# STM32F405.net
KiCad netlist of a schematic drawn in Altium Designer
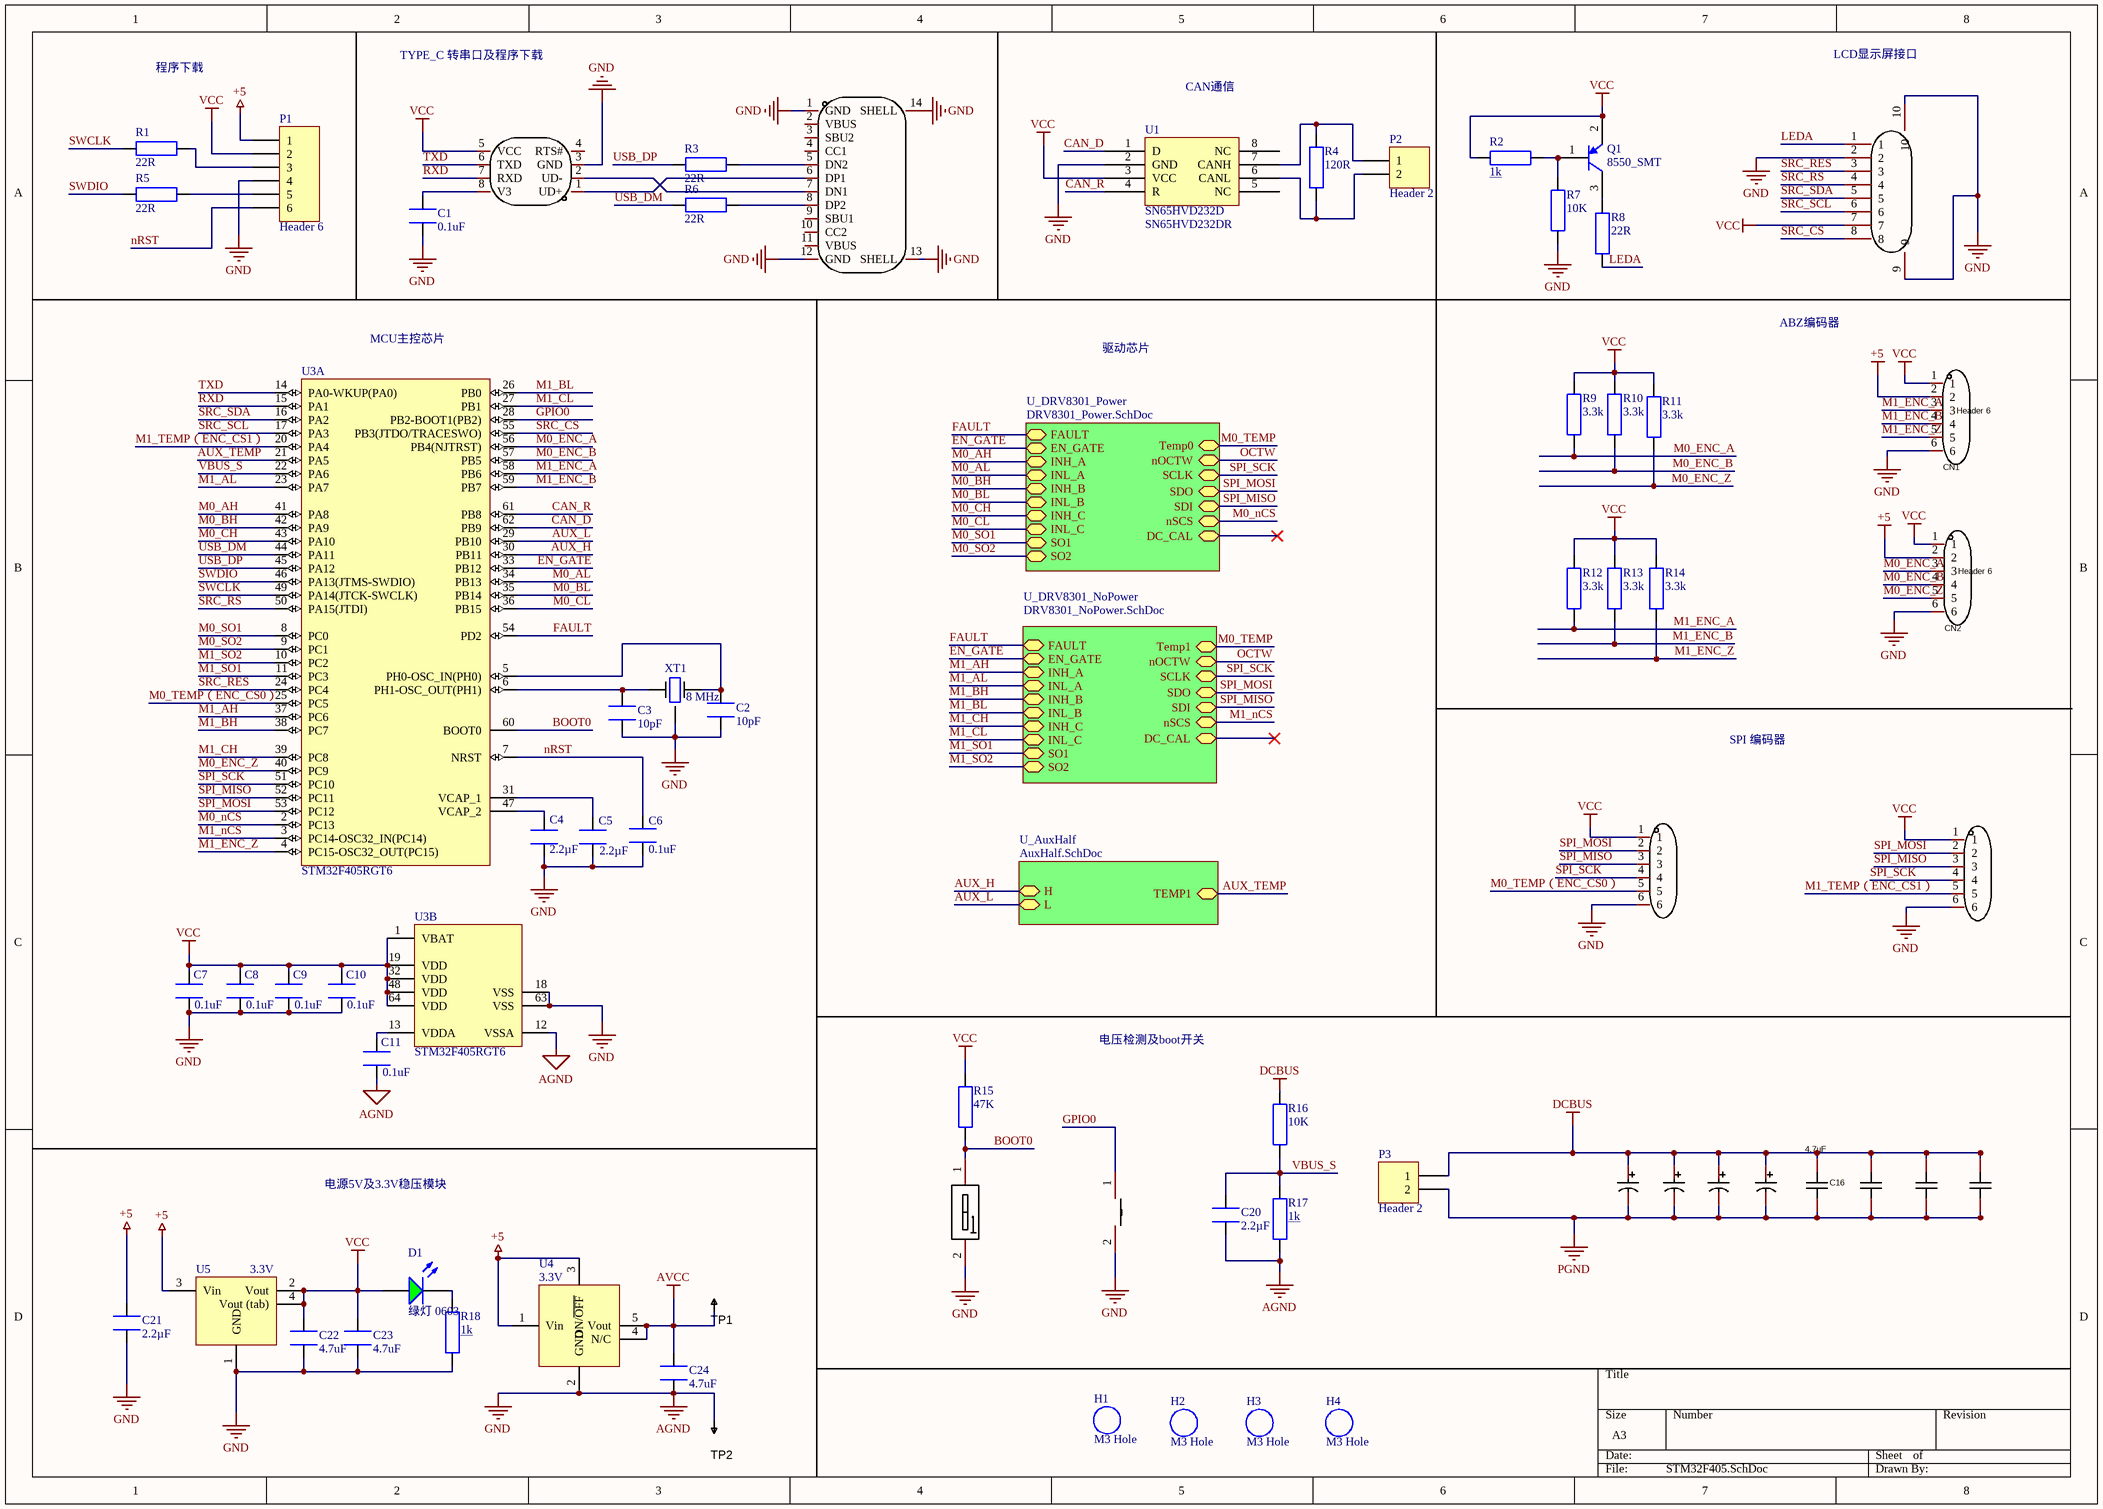
[diagram p0: STM32F405.SchDoc]

(export (version "E")
  (design (tool "Eeschema 10.0.6"))
  (components
    (comp (ref "C1")
      (value "0.1uF")
      (footprint "CAPC1608X09L")
      (description "CAP CER 0.1UF 50V X7R 0603")
      (fields
        (field (name "MANUFACTURER") "Murata Electronics North America")
        (field (name "MANUFACTURER PART NUMBER") "GRM188R71H104KA93D")
      )
      (libsource (lib "two_ax_PCB") (part "GRM188R71H104KA93D"))
    )
    (comp (ref "C2")
      (value "10pF")
      (footprint "CAPC1608X09L")
      (description "CAP CER 10PF 50V NP0 0603")
      (fields
        (field (name "MANUFACTURER") "Murata Electronics North America")
        (field (name "MANUFACTURER PART NUMBER") "GRM1885C1H100JA01D")
      )
      (libsource (lib "two_ax_PCB") (part "GRM1885C1H100JA01D"))
    )
    (comp (ref "C3")
      (value "10pF")
      (footprint "CAPC1608X09L")
      (description "CAP CER 10PF 50V NP0 0603")
      (fields
        (field (name "MANUFACTURER") "Murata Electronics North America")
        (field (name "MANUFACTURER PART NUMBER") "GRM1885C1H100JA01D")
      )
      (libsource (lib "two_ax_PCB") (part "GRM1885C1H100JA01D"))
    )
    (comp (ref "C4")
      (value "2.2µF")
      (footprint "CAPC1608X09L")
      (description "CAP CER 2.2UF 16V X5R 0603")
      (fields
        (field (name "MANUFACTURER") "Murata Electronics North America")
        (field (name "MANUFACTURER PART NUMBER") "GRM188R61C225KE15D")
      )
      (libsource (lib "two_ax_PCB") (part "GRM188R61C225KE15D"))
    )
    (comp (ref "C5")
      (value "2.2µF")
      (footprint "CAPC1608X09L")
      (description "CAP CER 2.2UF 16V X5R 0603")
      (fields
        (field (name "MANUFACTURER") "Murata Electronics North America")
        (field (name "MANUFACTURER PART NUMBER") "GRM188R61C225KE15D")
      )
      (libsource (lib "two_ax_PCB") (part "GRM188R61C225KE15D"))
    )
    (comp (ref "C6")
      (value "0.1uF")
      (footprint "CAPC1608X09L")
      (description "CAP CER 0.1UF 50V X7R 0603")
      (fields
        (field (name "MANUFACTURER") "Murata Electronics North America")
        (field (name "MANUFACTURER PART NUMBER") "GRM188R71H104KA93D")
      )
      (libsource (lib "two_ax_PCB") (part "GRM188R71H104KA93D"))
    )
    (comp (ref "C7")
      (value "0.1uF")
      (footprint "CAPC1608X09L")
      (description "CAP CER 0.1UF 50V X7R 0603")
      (fields
        (field (name "MANUFACTURER") "Murata Electronics North America")
        (field (name "MANUFACTURER PART NUMBER") "GRM188R71H104KA93D")
      )
      (libsource (lib "two_ax_PCB") (part "GRM188R71H104KA93D"))
    )
    (comp (ref "C8")
      (value "0.1uF")
      (footprint "CAPC1608X09L")
      (description "CAP CER 0.1UF 50V X7R 0603")
      (fields
        (field (name "MANUFACTURER") "Murata Electronics North America")
        (field (name "MANUFACTURER PART NUMBER") "GRM188R71H104KA93D")
      )
      (libsource (lib "two_ax_PCB") (part "GRM188R71H104KA93D"))
    )
    (comp (ref "C9")
      (value "0.1uF")
      (footprint "CAPC1608X09L")
      (description "CAP CER 0.1UF 50V X7R 0603")
      (fields
        (field (name "MANUFACTURER") "Murata Electronics North America")
        (field (name "MANUFACTURER PART NUMBER") "GRM188R71H104KA93D")
      )
      (libsource (lib "two_ax_PCB") (part "GRM188R71H104KA93D"))
    )
    (comp (ref "C10")
      (value "0.1uF")
      (footprint "CAPC1608X09L")
      (description "CAP CER 0.1UF 50V X7R 0603")
      (fields
        (field (name "MANUFACTURER") "Murata Electronics North America")
        (field (name "MANUFACTURER PART NUMBER") "GRM188R71H104KA93D")
      )
      (libsource (lib "two_ax_PCB") (part "GRM188R71H104KA93D"))
    )
    (comp (ref "C11")
      (value "0.1uF")
      (footprint "CAPC1608X09L")
      (description "CAP CER 0.1UF 50V X7R 0603")
      (fields
        (field (name "MANUFACTURER") "Murata Electronics North America")
        (field (name "MANUFACTURER PART NUMBER") "GRM188R71H104KA93D")
      )
      (libsource (lib "two_ax_PCB") (part "GRM188R71H104KA93D"))
    )
    (comp (ref "C12")
      (value "220uF")
      (footprint "CAP-SMD_BD12.5-L13.0-W13.0-FD")
      (description "63v 220uF 贴片电容")
      (fields (field (name "MANUFACTURER") "lelon(立隆)") (field (name "MANUFACTURER PART") "VZH221M1JTR-1313"))
      (libsource (lib "CustomComponents") (part "VZH221M1JTR-1313"))
    )
    (comp (ref "C13")
      (value "220uF")
      (footprint "CAP-SMD_BD12.5-L13.0-W13.0-FD")
      (description "63v 220uF 贴片电容")
      (fields (field (name "MANUFACTURER") "lelon(立隆)") (field (name "MANUFACTURER PART") "VZH221M1JTR-1313"))
      (libsource (lib "CustomComponents") (part "VZH221M1JTR-1313"))
    )
    (comp (ref "C14")
      (value "220uF")
      (footprint "CAP-SMD_BD12.5-L13.0-W13.0-FD")
      (description "63v 220uF 贴片电容")
      (fields (field (name "MANUFACTURER") "lelon(立隆)") (field (name "MANUFACTURER PART") "VZH221M1JTR-1313"))
      (libsource (lib "CustomComponents") (part "VZH221M1JTR-1313"))
    )
    (comp (ref "C15")
      (value "220uF")
      (footprint "CAP-SMD_BD12.5-L13.0-W13.0-FD")
      (description "63v 220uF 贴片电容")
      (fields (field (name "MANUFACTURER") "lelon(立隆)") (field (name "MANUFACTURER PART") "VZH221M1JTR-1313"))
      (libsource (lib "CustomComponents") (part "VZH221M1JTR-1313"))
    )
    (comp (ref "C16")
      (value "4.7uF")
      (footprint "C1210")
      (description "4.7uF 63V 1210封装")
      (fields
        (field (name "MANUFACTURER") "SANYEAR(叁叶源)")
        (field (name "MANUFACTURER PART") "C1210X7R475K630NT")
      )
      (libsource (lib "CustomComponents") (part "C1210X7R475K630NT"))
    )
    (comp (ref "C17")
      (value "4.7uF")
      (footprint "C1210")
      (description "4.7uF 63V 1210封装")
      (fields
        (field (name "MANUFACTURER") "SANYEAR(叁叶源)")
        (field (name "MANUFACTURER PART") "C1210X7R475K630NT")
      )
      (libsource (lib "CustomComponents") (part "C1210X7R475K630NT"))
    )
    (comp (ref "C18")
      (value "4.7uF")
      (footprint "C1210")
      (description "4.7uF 63V 1210封装")
      (fields
        (field (name "MANUFACTURER") "SANYEAR(叁叶源)")
        (field (name "MANUFACTURER PART") "C1210X7R475K630NT")
      )
      (libsource (lib "CustomComponents") (part "C1210X7R475K630NT"))
    )
    (comp (ref "C19")
      (value "4.7uF")
      (footprint "C1210")
      (description "4.7uF 63V 1210封装")
      (fields
        (field (name "MANUFACTURER") "SANYEAR(叁叶源)")
        (field (name "MANUFACTURER PART") "C1210X7R475K630NT")
      )
      (libsource (lib "CustomComponents") (part "C1210X7R475K630NT"))
    )
    (comp (ref "C20")
      (value "2.2µF")
      (footprint "CAPC1608X09L")
      (description "CAP CER 2.2UF 16V X5R 0603")
      (fields
        (field (name "MANUFACTURER") "Murata Electronics North America")
        (field (name "MANUFACTURER PART NUMBER") "GRM188R61C225KE15D")
      )
      (libsource (lib "CustomComponents") (part "GRM188R61C225KE15D"))
    )
    (comp (ref "C21")
      (value "2.2µF")
      (footprint "CAPC1608X09L")
      (description "CAP CER 2.2UF 16V X5R 0603")
      (fields
        (field (name "MANUFACTURER") "Murata Electronics North America")
        (field (name "MANUFACTURER PART NUMBER") "GRM188R61C225KE15D")
      )
      (libsource (lib "CustomComponents") (part "GRM188R61C225KE15D"))
    )
    (comp (ref "C22")
      (value "4.7uF")
      (footprint "CAPC2012X09N")
      (description "CAP CER 4.7UF 50V X5R 0805")
      (fields
        (field (name "MANUFACTURER") "Murata Electronics North America")
        (field (name "TOLERANCE") "±10%")
      )
      (libsource (lib "CustomComponents") (part "GRM21BR61H475KE51L"))
    )
    (comp (ref "C23")
      (value "4.7uF")
      (footprint "CAPC2012X09N")
      (description "CAP CER 4.7UF 50V X5R 0805")
      (fields
        (field (name "MANUFACTURER") "Murata Electronics North America")
        (field (name "TOLERANCE") "±10%")
      )
      (libsource (lib "CustomComponents") (part "GRM21BR61H475KE51L"))
    )
    (comp (ref "C24")
      (value "4.7uF")
      (footprint "CAPC2012X09N")
      (description "CAP CER 4.7UF 50V X5R 0805")
      (fields
        (field (name "MANUFACTURER") "Murata Electronics North America")
        (field (name "TOLERANCE") "±10%")
      )
      (libsource (lib "CustomComponents") (part "GRM21BR61H475KE51L"))
    )
    (comp (ref "CN1")
      (value "Header 6")
      (footprint "XH254-6")
      (description "6p 90度弯插")
      (fields
        (field (name "MANUFACTURER") "XKB Connection(中国星坤)")
        (field (name "MANUFACTURER PART") "X8821WR-06S-N0SN")
      )
      (libsource (lib "CustomComponents") (part "X8821WR-06S-N0SN"))
    )
    (comp (ref "CN2")
      (value "Header 6")
      (footprint "XH254-6")
      (description "6p 90度弯插")
      (fields
        (field (name "MANUFACTURER") "XKB Connection(中国星坤)")
        (field (name "MANUFACTURER PART") "X8821WR-06S-N0SN")
      )
      (libsource (lib "CustomComponents") (part "X8821WR-06S-N0SN"))
    )
    (comp (ref "CN3")
      (value "X8821WR-06S-N0SN")
      (footprint "CONN-TH_6P-P2.50_X8821WR-06S-N2SN")
      (description "6p 90度弯插")
      (fields (field (name "MANUFACTURER") "XKB Connection(中国星坤)"))
      (libsource (lib "CustomComponents") (part "X8821WR-06S-N0SN"))
    )
    (comp (ref "CN4")
      (value "X8821WR-06S-N0SN")
      (footprint "CONN-TH_6P-P2.50_X8821WR-06S-N2SN")
      (description "6p 90度弯插")
      (fields (field (name "MANUFACTURER") "XKB Connection(中国星坤)"))
      (libsource (lib "CustomComponents") (part "X8821WR-06S-N0SN"))
    )
    (comp (ref "D1")
      (value "绿灯 0603")
      (footprint "0603_LED_S1")
      (description "发光二极管")
      (libsource (lib "02-Miscellaneous_Devices_ZSF_Library") (part "0603 绿灯"))
    )
    (comp (ref "FPC1")
      (value "AFC01-S08FCA-00")
      (footprint "FPC-SMD_P0.50-8P_FGS-XJ-H2.0")
      (description "显示屏 8P FPC接口")
      (fields (field (name "MANUFACTURER") "JS(钜硕电子)"))
      (libsource (lib "CustomComponents") (part "AFC01-S08FCA-00"))
    )
    (comp (ref "H1")
      (value "M3 Hole")
      (footprint "M3 Hole")
      (description "M3 Hole with no copper")
      (libsource (lib "two_ax_PCB") (part "M3 Hole"))
    )
    (comp (ref "H2")
      (value "M3 Hole")
      (footprint "M3 Hole")
      (description "M3 Hole with no copper")
      (libsource (lib "two_ax_PCB") (part "M3 Hole"))
    )
    (comp (ref "H3")
      (value "M3 Hole")
      (footprint "M3 Hole")
      (description "M3 Hole with no copper")
      (libsource (lib "two_ax_PCB") (part "M3 Hole"))
    )
    (comp (ref "H4")
      (value "M3 Hole")
      (footprint "M3 Hole")
      (description "M3 Hole with no copper")
      (libsource (lib "two_ax_PCB") (part "M3 Hole"))
    )
    (comp (ref "P1")
      (value "Header 6")
      (footprint "SIP-6")
      (description "Header, 6-Pin")
      (fields (field (name "PUBLISHER") "Altium Limited"))
      (libsource (lib "01-Connect_IntegratedLibrary") (part "Header 6"))
    )
    (comp (ref "P2")
      (value "Header 2")
      (footprint "XH254-2")
      (description "Header, 2-Pin")
      (fields (field (name "PUBLISHER") "Altium Limited"))
      (libsource (lib "") (part "Header 2_1"))
    )
    (comp (ref "P3")
      (value "Header 2")
      (footprint "CONN-TH_XT30U-M")
      (description "Header, 2-Pin")
      (fields (field (name "PUBLISHER") "Altium Limited"))
      (libsource (lib "01-Connect_IntegratedLibrary") (part "Header 2"))
    )
    (comp (ref "Q1")
      (value "8550_SMT")
      (footprint "SOT-23(SOT-23-3)")
      (description "PNP型小功率三极管")
      (libsource (lib "02-Miscellaneous_Devices_ZSF_Library") (part "8550_SOT-23"))
    )
    (comp (ref "R1")
      (value "22R")
      (footprint "RESC1608X55N")
      (description "RES SMD 22 OHM 1% 1/10W 0603")
      (fields
        (field (name "MANUFACTURER") "Yageo")
        (field (name "MANUFACTURER PART NUMBER") "RC0603FR-0722RL")
      )
      (libsource (lib "CustomComponents") (part "RC0603FR-0722RL"))
    )
    (comp (ref "R2")
      (value "1k")
      (footprint "RESC1608X55N")
      (description "RES SMD 1K OHM 1% 1/10W 0603")
      (fields (field (name "MANUFACTURER") "Yageo") (field (name "TOLERANCE") "±1%"))
      (libsource (lib "CustomComponents") (part "RC0603FR-071KL"))
    )
    (comp (ref "R3")
      (value "22R")
      (footprint "RESC1608X55N")
      (description "RES SMD 22 OHM 1% 1/10W 0603")
      (fields
        (field (name "MANUFACTURER") "Yageo")
        (field (name "MANUFACTURER PART NUMBER") "RC0603FR-0722RL")
      )
      (libsource (lib "CustomComponents") (part "RC0603FR-0722RL"))
    )
    (comp (ref "R4")
      (value "120R")
      (footprint "RESC1608X55N")
      (description "RES SMD 120 OHM 1% 1/10W 0603")
      (fields
        (field (name "MANUFACTURER") "Yageo")
        (field (name "MANUFACTURER PART NUMBER") "RC0603FR-07120RL")
      )
      (libsource (lib "CustomComponents") (part "RC0603FR-07120RL"))
    )
    (comp (ref "R5")
      (value "22R")
      (footprint "RESC1608X55N")
      (description "RES SMD 22 OHM 1% 1/10W 0603")
      (fields
        (field (name "MANUFACTURER") "Yageo")
        (field (name "MANUFACTURER PART NUMBER") "RC0603FR-0722RL")
      )
      (libsource (lib "CustomComponents") (part "RC0603FR-0722RL"))
    )
    (comp (ref "R6")
      (value "22R")
      (footprint "RESC1608X55N")
      (description "RES SMD 22 OHM 1% 1/10W 0603")
      (fields
        (field (name "MANUFACTURER") "Yageo")
        (field (name "MANUFACTURER PART NUMBER") "RC0603FR-0722RL")
      )
      (libsource (lib "CustomComponents") (part "RC0603FR-0722RL"))
    )
    (comp (ref "R7")
      (value "10K")
      (footprint "RESC1608X55N")
      (description "RES SMD 10K OHM 1% 1/10W 0603")
      (fields
        (field (name "MANUFACTURER") "Yageo")
        (field (name "MANUFACTURER PART NUMBER") "RC0603FR-0710KL")
      )
      (libsource (lib "CustomComponents") (part "RC0603FR-0710KL"))
    )
    (comp (ref "R8")
      (value "22R")
      (footprint "RESC1608X55N")
      (description "RES SMD 22 OHM 1% 1/10W 0603")
      (fields
        (field (name "MANUFACTURER") "Yageo")
        (field (name "MANUFACTURER PART NUMBER") "RC0603FR-0722RL")
      )
      (libsource (lib "CustomComponents") (part "RC0603FR-0722RL"))
    )
    (comp (ref "R9")
      (value "3.3k")
      (footprint "RESC1608X55N")
      (description "RES SMD 3.3K OHM 1% 1/10W 0603")
      (fields
        (field (name "MANUFACTURER") "Yageo")
        (field (name "MANUFACTURER PART NUMBER") "RC0603FR-073K3L")
      )
      (libsource (lib "CustomComponents") (part "RC0603FR-073K3L"))
    )
    (comp (ref "R10")
      (value "3.3k")
      (footprint "RESC1608X55N")
      (description "RES SMD 3.3K OHM 1% 1/10W 0603")
      (fields
        (field (name "MANUFACTURER") "Yageo")
        (field (name "MANUFACTURER PART NUMBER") "RC0603FR-073K3L")
      )
      (libsource (lib "CustomComponents") (part "RC0603FR-073K3L"))
    )
    (comp (ref "R11")
      (value "3.3k")
      (footprint "RESC1608X55N")
      (description "RES SMD 3.3K OHM 1% 1/10W 0603")
      (fields
        (field (name "MANUFACTURER") "Yageo")
        (field (name "MANUFACTURER PART NUMBER") "RC0603FR-073K3L")
      )
      (libsource (lib "CustomComponents") (part "RC0603FR-073K3L"))
    )
    (comp (ref "R12")
      (value "3.3k")
      (footprint "RESC1608X55N")
      (description "RES SMD 3.3K OHM 1% 1/10W 0603")
      (fields
        (field (name "MANUFACTURER") "Yageo")
        (field (name "MANUFACTURER PART NUMBER") "RC0603FR-073K3L")
      )
      (libsource (lib "CustomComponents") (part "RC0603FR-073K3L"))
    )
    (comp (ref "R13")
      (value "3.3k")
      (footprint "RESC1608X55N")
      (description "RES SMD 3.3K OHM 1% 1/10W 0603")
      (fields
        (field (name "MANUFACTURER") "Yageo")
        (field (name "MANUFACTURER PART NUMBER") "RC0603FR-073K3L")
      )
      (libsource (lib "CustomComponents") (part "RC0603FR-073K3L"))
    )
    (comp (ref "R14")
      (value "3.3k")
      (footprint "RESC1608X55N")
      (description "RES SMD 3.3K OHM 1% 1/10W 0603")
      (fields
        (field (name "MANUFACTURER") "Yageo")
        (field (name "MANUFACTURER PART NUMBER") "RC0603FR-073K3L")
      )
      (libsource (lib "CustomComponents") (part "RC0603FR-073K3L"))
    )
    (comp (ref "R15")
      (value "47K")
      (footprint "RESC1608X55N")
      (description "RES SMD 47K OHM 1% 1/10W 0603")
      (fields
        (field (name "MANUFACTURER") "Yageo")
        (field (name "MANUFACTURER PART NUMBER") "RC0603FR-0747KL")
      )
      (libsource (lib "two_ax_PCB") (part "RC0603FR-0747KL"))
    )
    (comp (ref "R16")
      (value "10K")
      (footprint "RESC1608X55N")
      (description "RES SMD 10K OHM 1% 1/10W 0603")
      (fields
        (field (name "MANUFACTURER") "Yageo")
        (field (name "MANUFACTURER PART NUMBER") "RC0603FR-0710KL")
      )
      (libsource (lib "CustomComponents") (part "RC0603FR-0710KL"))
    )
    (comp (ref "R17")
      (value "1k")
      (footprint "RESC1608X55N")
      (description "RES SMD 1K OHM 1% 1/10W 0603")
      (fields (field (name "MANUFACTURER") "Yageo") (field (name "TOLERANCE") "±1%"))
      (libsource (lib "CustomComponents") (part "RC0603FR-071KL"))
    )
    (comp (ref "R18")
      (value "1k")
      (footprint "RESC1608X55N")
      (description "RES SMD 1K OHM 1% 1/10W 0603")
      (fields (field (name "MANUFACTURER") "Yageo") (field (name "TOLERANCE") "±1%"))
      (libsource (lib "CustomComponents") (part "RC0603FR-071KL"))
    )
    (comp (ref "SW1")
      (value "DSWB01LHGET")
      (footprint "SW-TH_DSWB01LHGET")
      (description "单刀拨码开关")
      (fields (field (name "MANUFACTURER") "YE"))
      (libsource (lib "CustomComponents") (part "DSWB01LHGET"))
    )
    (comp (ref "SW2")
      (value "TS-1101-C-W")
      (footprint "SW-SMD_L6.0-W3.3-LS8.0")
      (description "轻触开关")
      (fields (field (name "MANUFACTURER") "XKB Connectivity(中国星坤)"))
      (libsource (lib "CustomComponents") (part "TS-1101-C-W"))
    )
    (comp (ref "TP1")
      (value "TESTPOINT")
      (footprint "TP-R30")
      (description "SMD test pin")
      (libsource (lib "two_ax_PCB") (part "TESTPOINT"))
    )
    (comp (ref "TP2")
      (value "TESTPOINT")
      (footprint "TP-R30")
      (description "SMD test pin")
      (libsource (lib "two_ax_PCB") (part "TESTPOINT"))
    )
    (comp (ref "U1")
      (value "SN65HVD232D")
      (footprint "SOIC127P600X175-8N")
      (fields
        (field (name "MANUFACTURER") "Texas Instruments")
        (field (name "MANUFACTURER PART NUMBER") "SN65HVD232DR")
      )
      (libsource (lib "CustomComponents") (part "SN65HVD232D"))
    )
    (comp (ref "U2")
      (value "CH340N")
      (footprint "ch340N  SOP-8_L4.9-W3.9-P1.27-LS6.0-BL")
      (fields (field (name "MANUFACTURER") "WCH(南京沁恒)"))
      (libsource (lib "CustomComponents") (part "CH340N"))
    )
    (comp (ref "U3")
      (value "STM32F405RGT6")
      (footprint "STM-LQFP64_N")
      (fields (field (name "MANUFACTURER") "STMicroelectronics"))
      (libsource (lib "STMicroelectronics STM32 F4") (part "STM32F405RGT6"))
    )
    (comp (ref "U4")
      (value "3.3V")
      (footprint "SOT23-5")
      (description "IC REG LDO 3.3V 0.25A SOT23-5")
      (fields (field (name "MANUFACTURER") "Texas Instruments"))
      (libsource (lib "CustomComponents") (part "LP5907MFX-3.3/NOPB"))
    )
    (comp (ref "U5")
      (value "3.3V")
      (footprint "SOT223")
      (description "IC REG LDO 3.3V 1A SOT223")
      (fields (field (name "MANUFACTURER") "Diodes Incorporated"))
      (libsource (lib "CustomComponents") (part "AZ1117EH-3.3TRG1"))
    )
    (comp (ref "USB1")
      (value "TYPE-C 16PIN 2MD(073)")
      (footprint "USB-C-SMD_TYPE-C-16PIN-2MD-073")
      (fields (field (name "MANUFACTURER") "SHOU HAN(首韩)"))
      (libsource (lib "CustomComponents") (part "TYPE-C 16PIN 2MD(073)"))
    )
    (comp (ref "XT1")
      (value "8 MHz")
      (footprint "DFN220P320X110-4N")
      (description "Crystal 8MHz ±10ppm 10pF 200 Ohm -10°C ~ 60°C Surface Mount 4-SMD, No Lead (DFN, LCC)")
      (fields
        (field (name "MANUFACTURER") "Abracon LLC")
        (field (name "MANUFACTURER PART NUMBER") "ABM3B-8.000MHZ-10-1-U-T")
      )
      (libsource (lib "two_ax_PCB") (part "ABM3B-8.000MHZ-10-1-U-T"))
    )
  )
  (nets
    (net (code "1") (name "+5") (class "Default")
      (node (ref "C21") (pin "2") (pinfunction "2_2") (pintype "passive"))
      (node (ref "CN1") (pin "2") (pinfunction "2_2") (pintype "passive"))
      (node (ref "CN2") (pin "2") (pinfunction "2_2") (pintype "passive"))
      (node (ref "P1") (pin "1") (pinfunction "1_1") (pintype "passive"))
      (node (ref "U4") (pin "1") (pinfunction "Vin_1") (pintype "passive"))
      (node (ref "U4") (pin "3") (pinfunction "ON/~{OFF}_3") (pintype "passive"))
      (node (ref "U5") (pin "3") (pinfunction "Vin_3") (pintype "passive"))
    )
    (net (code "2") (name "/AUX_H") (class "Default")
      (node (ref "U3") (pin "30") (pinfunction "PB11_30") (pintype "bidirectional"))
    )
    (net (code "3") (name "/AUX_L") (class "Default")
      (node (ref "U3") (pin "29") (pinfunction "PB10_29") (pintype "bidirectional"))
    )
    (net (code "4") (name "/AUX_TEMP") (class "Default")
      (node (ref "U3") (pin "21") (pinfunction "PA5_21") (pintype "bidirectional"))
    )
    (net (code "5") (name "/BOOT0") (class "Default")
      (node (ref "R15") (pin "1") (pinfunction "0_1") (pintype "passive"))
      (node (ref "SW1") (pin "1") (pinfunction "A1_1") (pintype "passive"))
      (node (ref "U3") (pin "60") (pinfunction "BOOT0_60") (pintype "passive"))
    )
    (net (code "6") (name "/CAN_D") (class "Default")
      (node (ref "U1") (pin "1") (pinfunction "D_1") (pintype "passive"))
      (node (ref "U3") (pin "62") (pinfunction "PB9_62") (pintype "bidirectional"))
    )
    (net (code "7") (name "/CAN_R") (class "Default")
      (node (ref "U1") (pin "4") (pinfunction "R_4") (pintype "passive"))
      (node (ref "U3") (pin "61") (pinfunction "PB8_61") (pintype "bidirectional"))
    )
    (net (code "10") (name "/EN_GATE") (class "Default")
      (node (ref "U3") (pin "33") (pinfunction "PB12_33") (pintype "bidirectional"))
    )
    (net (code "11") (name "/FAULT") (class "Default")
      (node (ref "U3") (pin "54") (pinfunction "PD2_54") (pintype "bidirectional"))
    )
    (net (code "12") (name "/GPIO0") (class "Default")
      (node (ref "SW2") (pin "1") (pinfunction "1_1") (pintype "passive"))
      (node (ref "U3") (pin "28") (pinfunction "PB2-BOOT1(PB2)_28") (pintype "bidirectional"))
    )
    (net (code "13") (name "/LEDA") (class "Default")
      (node (ref "FPC1") (pin "1") (pinfunction "1_1") (pintype "passive"))
      (node (ref "R8") (pin "1") (pinfunction "0_1") (pintype "passive"))
    )
    (net (code "14") (name "/M0_AH") (class "Default")
      (node (ref "U3") (pin "41") (pinfunction "PA8_41") (pintype "bidirectional"))
    )
    (net (code "15") (name "/M0_AL") (class "Default")
      (node (ref "U3") (pin "34") (pinfunction "PB13_34") (pintype "bidirectional"))
    )
    (net (code "16") (name "/M0_BH") (class "Default")
      (node (ref "U3") (pin "42") (pinfunction "PA9_42") (pintype "bidirectional"))
    )
    (net (code "17") (name "/M0_BL") (class "Default")
      (node (ref "U3") (pin "35") (pinfunction "PB14_35") (pintype "bidirectional"))
    )
    (net (code "18") (name "/M0_CH") (class "Default")
      (node (ref "U3") (pin "43") (pinfunction "PA10_43") (pintype "bidirectional"))
    )
    (net (code "19") (name "/M0_CL") (class "Default")
      (node (ref "U3") (pin "36") (pinfunction "PB15_36") (pintype "bidirectional"))
    )
    (net (code "20") (name "/M0_ENC_A") (class "Default")
      (node (ref "CN2") (pin "3") (pinfunction "3_3") (pintype "passive"))
      (node (ref "R9") (pin "1") (pinfunction "0_1") (pintype "passive"))
      (node (ref "U3") (pin "56") (pinfunction "PB4(NJTRST)_56") (pintype "bidirectional"))
    )
    (net (code "21") (name "/M0_ENC_B") (class "Default")
      (node (ref "CN2") (pin "4") (pinfunction "4_4") (pintype "passive"))
      (node (ref "R10") (pin "1") (pinfunction "0_1") (pintype "passive"))
      (node (ref "U3") (pin "57") (pinfunction "PB5_57") (pintype "bidirectional"))
    )
    (net (code "22") (name "/M0_ENC_Z") (class "Default")
      (node (ref "CN2") (pin "5") (pinfunction "5_5") (pintype "passive"))
      (node (ref "R11") (pin "1") (pinfunction "0_1") (pintype "passive"))
      (node (ref "U3") (pin "40") (pinfunction "PC9_40") (pintype "bidirectional"))
    )
    (net (code "23") (name "/M0_SO1") (class "Default")
      (node (ref "U3") (pin "8") (pinfunction "PC0_8") (pintype "bidirectional"))
    )
    (net (code "24") (name "/M0_SO2") (class "Default")
      (node (ref "U3") (pin "9") (pinfunction "PC1_9") (pintype "bidirectional"))
    )
    (net (code "26") (name "/M0_TEMP（ENC_CS0）") (class "Default")
      (node (ref "CN3") (pin "5") (pinfunction "5_5") (pintype "passive"))
      (node (ref "U3") (pin "25") (pinfunction "PC5_25") (pintype "bidirectional"))
    )
    (net (code "27") (name "/M0_nCS") (class "Default")
      (node (ref "U3") (pin "2") (pinfunction "PC13_2") (pintype "bidirectional"))
    )
    (net (code "28") (name "/M1_AH") (class "Default")
      (node (ref "U3") (pin "37") (pinfunction "PC6_37") (pintype "bidirectional"))
    )
    (net (code "29") (name "/M1_AL") (class "Default")
      (node (ref "U3") (pin "23") (pinfunction "PA7_23") (pintype "bidirectional"))
    )
    (net (code "30") (name "/M1_BH") (class "Default")
      (node (ref "U3") (pin "38") (pinfunction "PC7_38") (pintype "bidirectional"))
    )
    (net (code "31") (name "/M1_BL") (class "Default")
      (node (ref "U3") (pin "26") (pinfunction "PB0_26") (pintype "bidirectional"))
    )
    (net (code "32") (name "/M1_CH") (class "Default")
      (node (ref "U3") (pin "39") (pinfunction "PC8_39") (pintype "bidirectional"))
    )
    (net (code "33") (name "/M1_CL") (class "Default")
      (node (ref "U3") (pin "27") (pinfunction "PB1_27") (pintype "bidirectional"))
    )
    (net (code "34") (name "/M1_ENC_A") (class "Default")
      (node (ref "CN1") (pin "3") (pinfunction "3_3") (pintype "passive"))
      (node (ref "R12") (pin "1") (pinfunction "0_1") (pintype "passive"))
      (node (ref "U3") (pin "58") (pinfunction "PB6_58") (pintype "bidirectional"))
    )
    (net (code "35") (name "/M1_ENC_B") (class "Default")
      (node (ref "CN1") (pin "4") (pinfunction "4_4") (pintype "passive"))
      (node (ref "R13") (pin "1") (pinfunction "0_1") (pintype "passive"))
      (node (ref "U3") (pin "59") (pinfunction "PB7_59") (pintype "bidirectional"))
    )
    (net (code "36") (name "/M1_ENC_Z") (class "Default")
      (node (ref "CN1") (pin "5") (pinfunction "5_5") (pintype "passive"))
      (node (ref "R14") (pin "1") (pinfunction "0_1") (pintype "passive"))
      (node (ref "U3") (pin "4") (pinfunction "PC15-OSC32_OUT(PC15)_4") (pintype "bidirectional"))
    )
    (net (code "37") (name "/M1_SO1") (class "Default")
      (node (ref "U3") (pin "11") (pinfunction "PC3_11") (pintype "bidirectional"))
    )
    (net (code "38") (name "/M1_SO2") (class "Default")
      (node (ref "U3") (pin "10") (pinfunction "PC2_10") (pintype "bidirectional"))
    )
    (net (code "39") (name "/M1_TEMP（ENC_CS1）") (class "Default")
      (node (ref "CN4") (pin "5") (pinfunction "5_5") (pintype "passive"))
      (node (ref "U3") (pin "20") (pinfunction "PA4_20") (pintype "bidirectional"))
    )
    (net (code "40") (name "/M1_nCS") (class "Default")
      (node (ref "U3") (pin "3") (pinfunction "PC14-OSC32_IN(PC14)_3") (pintype "bidirectional"))
    )
    (net (code "42") (name "/RXD") (class "Default")
      (node (ref "U2") (pin "7") (pinfunction "RXD_7") (pintype "passive"))
      (node (ref "U3") (pin "15") (pinfunction "PA1_15") (pintype "bidirectional"))
    )
    (net (code "43") (name "/SPI_MISO") (class "Default")
      (node (ref "CN3") (pin "3") (pinfunction "3_3") (pintype "passive"))
      (node (ref "CN4") (pin "3") (pinfunction "3_3") (pintype "passive"))
      (node (ref "U3") (pin "52") (pinfunction "PC11_52") (pintype "bidirectional"))
    )
    (net (code "44") (name "/SPI_MOSI") (class "Default")
      (node (ref "CN3") (pin "2") (pinfunction "2_2") (pintype "passive"))
      (node (ref "CN4") (pin "2") (pinfunction "2_2") (pintype "passive"))
      (node (ref "U3") (pin "53") (pinfunction "PC12_53") (pintype "bidirectional"))
    )
    (net (code "45") (name "/SPI_SCK") (class "Default")
      (node (ref "CN3") (pin "4") (pinfunction "4_4") (pintype "passive"))
      (node (ref "CN4") (pin "4") (pinfunction "4_4") (pintype "passive"))
      (node (ref "U3") (pin "51") (pinfunction "PC10_51") (pintype "bidirectional"))
    )
    (net (code "46") (name "/SRC_CS") (class "Default")
      (node (ref "FPC1") (pin "8") (pinfunction "8_8") (pintype "passive"))
      (node (ref "U3") (pin "55") (pinfunction "PB3(JTDO/TRACESWO)_55") (pintype "bidirectional"))
    )
    (net (code "47") (name "/SRC_RES") (class "Default")
      (node (ref "FPC1") (pin "3") (pinfunction "3_3") (pintype "passive"))
      (node (ref "U3") (pin "24") (pinfunction "PC4_24") (pintype "bidirectional"))
    )
    (net (code "48") (name "/SRC_RS") (class "Default")
      (node (ref "FPC1") (pin "4") (pinfunction "4_4") (pintype "passive"))
      (node (ref "U3") (pin "50") (pinfunction "PA15(JTDI)_50") (pintype "bidirectional"))
    )
    (net (code "49") (name "/SRC_SCL") (class "Default")
      (node (ref "FPC1") (pin "6") (pinfunction "6_6") (pintype "passive"))
      (node (ref "U3") (pin "17") (pinfunction "PA3_17") (pintype "bidirectional"))
    )
    (net (code "50") (name "/SRC_SDA") (class "Default")
      (node (ref "FPC1") (pin "5") (pinfunction "5_5") (pintype "passive"))
      (node (ref "U3") (pin "16") (pinfunction "PA2_16") (pintype "bidirectional"))
    )
    (net (code "51") (name "/SWCLK") (class "Default")
      (node (ref "R1") (pin "2") (pinfunction "0_2") (pintype "passive"))
      (node (ref "U3") (pin "49") (pinfunction "PA14(JTCK-SWCLK)_49") (pintype "bidirectional"))
    )
    (net (code "52") (name "/SWDIO") (class "Default")
      (node (ref "R5") (pin "2") (pinfunction "0_2") (pintype "passive"))
      (node (ref "U3") (pin "46") (pinfunction "PA13(JTMS-SWDIO)_46") (pintype "bidirectional"))
    )
    (net (code "53") (name "/TXD") (class "Default")
      (node (ref "U2") (pin "6") (pinfunction "TXD_6") (pintype "passive"))
      (node (ref "U3") (pin "14") (pinfunction "PA0-WKUP(PA0)_14") (pintype "bidirectional"))
    )
    (net (code "54") (name "/USB_DM") (class "Default")
      (node (ref "R6") (pin "2") (pinfunction "0_2") (pintype "passive"))
      (node (ref "U3") (pin "44") (pinfunction "PA11_44") (pintype "bidirectional"))
    )
    (net (code "55") (name "/USB_DP") (class "Default")
      (node (ref "R3") (pin "2") (pinfunction "0_2") (pintype "passive"))
      (node (ref "U3") (pin "45") (pinfunction "PA12_45") (pintype "bidirectional"))
    )
    (net (code "56") (name "/VBUS_S") (class "Default")
      (node (ref "C20") (pin "2") (pinfunction "2_2") (pintype "passive"))
      (node (ref "R16") (pin "1") (pinfunction "0_1") (pintype "passive"))
      (node (ref "R17") (pin "2") (pinfunction "0_2") (pintype "passive"))
      (node (ref "U3") (pin "22") (pinfunction "PA6_22") (pintype "bidirectional"))
    )
    (net (code "57") (name "/nRST") (class "Default")
      (node (ref "C6") (pin "2") (pinfunction "2_2") (pintype "passive"))
      (node (ref "P1") (pin "6") (pinfunction "6_6") (pintype "passive"))
      (node (ref "U3") (pin "7") (pinfunction "NRST_7") (pintype "bidirectional"))
    )
    (net (code "58") (name "AGND") (class "Default")
      (node (ref "C1") (pin "1") (pinfunction "1_1") (pintype "passive"))
      (node (ref "C10") (pin "1") (pinfunction "1_1") (pintype "passive"))
      (node (ref "C11") (pin "1") (pinfunction "1_1") (pintype "passive"))
      (node (ref "C2") (pin "2") (pinfunction "2_2") (pintype "passive"))
      (node (ref "C20") (pin "1") (pinfunction "1_1") (pintype "passive"))
      (node (ref "C21") (pin "1") (pinfunction "1_1") (pintype "passive"))
      (node (ref "C22") (pin "1") (pinfunction "1_1") (pintype "passive"))
      (node (ref "C23") (pin "1") (pinfunction "1_1") (pintype "passive"))
      (node (ref "C24") (pin "1") (pinfunction "1_1") (pintype "passive"))
      (node (ref "C3") (pin "2") (pinfunction "2_2") (pintype "passive"))
      (node (ref "C4") (pin "1") (pinfunction "1_1") (pintype "passive"))
      (node (ref "C5") (pin "1") (pinfunction "1_1") (pintype "passive"))
      (node (ref "C6") (pin "1") (pinfunction "1_1") (pintype "passive"))
      (node (ref "C7") (pin "1") (pinfunction "1_1") (pintype "passive"))
      (node (ref "C8") (pin "1") (pinfunction "1_1") (pintype "passive"))
      (node (ref "C9") (pin "1") (pinfunction "1_1") (pintype "passive"))
      (node (ref "CN1") (pin "6") (pinfunction "6_6") (pintype "passive"))
      (node (ref "CN2") (pin "6") (pinfunction "6_6") (pintype "passive"))
      (node (ref "CN3") (pin "6") (pinfunction "6_6") (pintype "passive"))
      (node (ref "CN4") (pin "6") (pinfunction "6_6") (pintype "passive"))
      (node (ref "FPC1") (pin "10") (pinfunction "10_10") (pintype "passive"))
      (node (ref "FPC1") (pin "2") (pinfunction "2_2") (pintype "passive"))
      (node (ref "FPC1") (pin "9") (pinfunction "9_9") (pintype "passive"))
      (node (ref "P1") (pin "4") (pinfunction "4_4") (pintype "passive"))
      (node (ref "R17") (pin "1") (pinfunction "0_1") (pintype "passive"))
      (node (ref "R18") (pin "1") (pinfunction "0_1") (pintype "passive"))
      (node (ref "R7") (pin "1") (pinfunction "0_1") (pintype "passive"))
      (node (ref "SW1") (pin "2") (pinfunction "2_2") (pintype "passive"))
      (node (ref "SW2") (pin "2") (pinfunction "2_2") (pintype "passive"))
      (node (ref "TP2") (pin "1") (pintype "passive"))
      (node (ref "U1") (pin "2") (pinfunction "GND_2") (pintype "passive"))
      (node (ref "U2") (pin "3") (pinfunction "GND_3") (pintype "passive"))
      (node (ref "U3") (pin "12") (pinfunction "VSSA_12") (pintype "power_in"))
      (node (ref "U3") (pin "18") (pinfunction "VSS_18") (pintype "power_in"))
      (node (ref "U3") (pin "63") (pinfunction "VSS_63") (pintype "power_in"))
      (node (ref "U4") (pin "2") (pinfunction "GND_2") (pintype "passive"))
      (node (ref "U5") (pin "1") (pinfunction "GND_1") (pintype "passive"))
      (node (ref "USB1") (pin "1") (pinfunction "GND_1") (pintype "passive"))
      (node (ref "USB1") (pin "12") (pinfunction "GND_12") (pintype "passive"))
      (node (ref "USB1") (pin "13") (pinfunction "SHELL_13") (pintype "passive"))
      (node (ref "USB1") (pin "14") (pinfunction "SHELL_14") (pintype "passive"))
      (node (ref "XT1") (pin "G") (pintype "passive"))
    )
    (net (code "59") (name "AVCC") (class "Default")
      (node (ref "C24") (pin "2") (pinfunction "2_2") (pintype "passive"))
      (node (ref "TP1") (pin "1") (pintype "passive"))
      (node (ref "U4") (pin "4") (pinfunction "N/C_4") (pintype "passive"))
      (node (ref "U4") (pin "5") (pinfunction "Vout_5") (pintype "passive"))
    )
    (net (code "60") (name "DCBUS") (class "Default")
      (node (ref "C12") (pin "1") (pinfunction "1_1") (pintype "passive"))
      (node (ref "C13") (pin "1") (pinfunction "1_1") (pintype "passive"))
      (node (ref "C14") (pin "1") (pinfunction "1_1") (pintype "passive"))
      (node (ref "C15") (pin "1") (pinfunction "1_1") (pintype "passive"))
      (node (ref "C16") (pin "1") (pinfunction "1_1") (pintype "passive"))
      (node (ref "C17") (pin "2") (pinfunction "2_2") (pintype "passive"))
      (node (ref "C18") (pin "2") (pinfunction "2_2") (pintype "passive"))
      (node (ref "C19") (pin "2") (pinfunction "2_2") (pintype "passive"))
      (node (ref "P3") (pin "1") (pinfunction "1_1") (pintype "passive"))
      (node (ref "R16") (pin "2") (pinfunction "0_2") (pintype "passive"))
    )
    (net (code "61") (name "Net-(D1-PadK)") (class "Default")
      (node (ref "D1") (pin "K") (pinfunction "K_K") (pintype "passive"))
      (node (ref "R18") (pin "2") (pinfunction "0_2") (pintype "passive"))
    )
    (net (code "62") (name "Net-(P1-Pad3)") (class "Default")
      (node (ref "P1") (pin "3") (pinfunction "3_3") (pintype "passive"))
      (node (ref "R1") (pin "1") (pinfunction "0_1") (pintype "passive"))
    )
    (net (code "63") (name "Net-(P1-Pad5)") (class "Default")
      (node (ref "P1") (pin "5") (pinfunction "5_5") (pintype "passive"))
      (node (ref "R5") (pin "1") (pinfunction "0_1") (pintype "passive"))
    )
    (net (code "64") (name "Net-(Q1-B)") (class "Default")
      (node (ref "Q1") (pin "1") (pinfunction "B_1") (pintype "passive"))
      (node (ref "R2") (pin "1") (pinfunction "0_1") (pintype "passive"))
      (node (ref "R7") (pin "2") (pinfunction "0_2") (pintype "passive"))
    )
    (net (code "65") (name "Net-(Q1-C)") (class "Default")
      (node (ref "Q1") (pin "3") (pinfunction "C_3") (pintype "passive"))
      (node (ref "R8") (pin "2") (pinfunction "0_2") (pintype "passive"))
    )
    (net (code "66") (name "Net-(U1-CANH)") (class "Default")
      (node (ref "P2") (pin "1") (pinfunction "1_1") (pintype "passive"))
      (node (ref "R4") (pin "2") (pinfunction "0_2") (pintype "passive"))
      (node (ref "U1") (pin "7") (pinfunction "CANH_7") (pintype "passive"))
    )
    (net (code "67") (name "Net-(U1-CANL)") (class "Default")
      (node (ref "P2") (pin "2") (pinfunction "2_2") (pintype "passive"))
      (node (ref "R4") (pin "1") (pinfunction "0_1") (pintype "passive"))
      (node (ref "U1") (pin "6") (pinfunction "CANL_6") (pintype "passive"))
    )
    (net (code "68") (name "Net-(U2-UD+)") (class "Default")
      (node (ref "U2") (pin "1") (pinfunction "UD+_1") (pintype "passive"))
      (node (ref "USB1") (pin "6") (pinfunction "DP1_6") (pintype "passive"))
    )
    (net (code "69") (name "Net-(U2-UD-)") (class "Default")
      (node (ref "U2") (pin "2") (pinfunction "UD-_2") (pintype "passive"))
      (node (ref "USB1") (pin "7") (pinfunction "DN1_7") (pintype "passive"))
    )
    (net (code "70") (name "Net-(U2-V3)") (class "Default")
      (node (ref "C1") (pin "2") (pinfunction "2_2") (pintype "passive"))
      (node (ref "U2") (pin "8") (pinfunction "V3_8") (pintype "passive"))
    )
    (net (code "71") (name "Net-(U3A-PH0-OSC_IN(PH0))") (class "Default")
      (node (ref "C2") (pin "1") (pinfunction "1_1") (pintype "passive"))
      (node (ref "U3") (pin "5") (pinfunction "PH0-OSC_IN(PH0)_5") (pintype "bidirectional"))
      (node (ref "XT1") (pin "3") (pintype "passive"))
    )
    (net (code "72") (name "Net-(U3A-PH1-OSC_OUT(PH1))") (class "Default")
      (node (ref "C3") (pin "1") (pinfunction "1_1") (pintype "passive"))
      (node (ref "U3") (pin "6") (pinfunction "PH1-OSC_OUT(PH1)_6") (pintype "bidirectional"))
      (node (ref "XT1") (pin "1") (pintype "passive"))
    )
    (net (code "73") (name "Net-(U3A-VCAP_1)") (class "Default")
      (node (ref "C5") (pin "2") (pinfunction "2_2") (pintype "passive"))
      (node (ref "U3") (pin "31") (pinfunction "VCAP_1_31") (pintype "power_in"))
    )
    (net (code "74") (name "Net-(U3A-VCAP_2)") (class "Default")
      (node (ref "C4") (pin "2") (pinfunction "2_2") (pintype "passive"))
      (node (ref "U3") (pin "47") (pinfunction "VCAP_2_47") (pintype "power_in"))
    )
    (net (code "75") (name "Net-(U3B-VDDA)") (class "Default")
      (node (ref "C11") (pin "2") (pinfunction "2_2") (pintype "passive"))
      (node (ref "U3") (pin "13") (pinfunction "VDDA_13") (pintype "power_in"))
    )
    (net (code "76") (name "Net-(USB1-DN2)") (class "Default")
      (node (ref "R3") (pin "1") (pinfunction "0_1") (pintype "passive"))
      (node (ref "USB1") (pin "5") (pinfunction "DN2_5") (pintype "passive"))
    )
    (net (code "77") (name "Net-(USB1-DP2)") (class "Default")
      (node (ref "R6") (pin "1") (pinfunction "0_1") (pintype "passive"))
      (node (ref "USB1") (pin "8") (pinfunction "DP2_8") (pintype "passive"))
    )
    (net (code "78") (name "PGND") (class "Default")
      (node (ref "C12") (pin "2") (pinfunction "2_2") (pintype "passive"))
      (node (ref "C13") (pin "2") (pinfunction "2_2") (pintype "passive"))
      (node (ref "C14") (pin "2") (pinfunction "2_2") (pintype "passive"))
      (node (ref "C15") (pin "2") (pinfunction "2_2") (pintype "passive"))
      (node (ref "C16") (pin "2") (pinfunction "2_2") (pintype "passive"))
      (node (ref "C17") (pin "1") (pinfunction "1_1") (pintype "passive"))
      (node (ref "C18") (pin "1") (pinfunction "1_1") (pintype "passive"))
      (node (ref "C19") (pin "1") (pinfunction "1_1") (pintype "passive"))
      (node (ref "P3") (pin "2") (pinfunction "2_2") (pintype "passive"))
    )
    (net (code "79") (name "VCC") (class "Default")
      (node (ref "C10") (pin "2") (pinfunction "2_2") (pintype "passive"))
      (node (ref "C22") (pin "2") (pinfunction "2_2") (pintype "passive"))
      (node (ref "C23") (pin "2") (pinfunction "2_2") (pintype "passive"))
      (node (ref "C7") (pin "2") (pinfunction "2_2") (pintype "passive"))
      (node (ref "C8") (pin "2") (pinfunction "2_2") (pintype "passive"))
      (node (ref "C9") (pin "2") (pinfunction "2_2") (pintype "passive"))
      (node (ref "CN1") (pin "1") (pinfunction "1_1") (pintype "passive"))
      (node (ref "CN2") (pin "1") (pinfunction "1_1") (pintype "passive"))
      (node (ref "CN3") (pin "1") (pinfunction "1_1") (pintype "passive"))
      (node (ref "CN4") (pin "1") (pinfunction "1_1") (pintype "passive"))
      (node (ref "D1") (pin "A") (pinfunction "A_A") (pintype "passive"))
      (node (ref "FPC1") (pin "7") (pinfunction "7_7") (pintype "passive"))
      (node (ref "P1") (pin "2") (pinfunction "2_2") (pintype "passive"))
      (node (ref "Q1") (pin "2") (pinfunction "E_2") (pintype "passive"))
      (node (ref "R10") (pin "2") (pinfunction "0_2") (pintype "passive"))
      (node (ref "R11") (pin "2") (pinfunction "0_2") (pintype "passive"))
      (node (ref "R12") (pin "2") (pinfunction "0_2") (pintype "passive"))
      (node (ref "R13") (pin "2") (pinfunction "0_2") (pintype "passive"))
      (node (ref "R14") (pin "2") (pinfunction "0_2") (pintype "passive"))
      (node (ref "R15") (pin "2") (pinfunction "0_2") (pintype "passive"))
      (node (ref "R2") (pin "2") (pinfunction "0_2") (pintype "passive"))
      (node (ref "R9") (pin "2") (pinfunction "0_2") (pintype "passive"))
      (node (ref "U1") (pin "3") (pinfunction "VCC_3") (pintype "passive"))
      (node (ref "U2") (pin "5") (pinfunction "VCC_5") (pintype "passive"))
      (node (ref "U3") (pin "1") (pinfunction "VBAT_1") (pintype "power_in"))
      (node (ref "U3") (pin "19") (pinfunction "VDD_19") (pintype "power_in"))
      (node (ref "U3") (pin "32") (pinfunction "VDD_32") (pintype "power_in"))
      (node (ref "U3") (pin "48") (pinfunction "VDD_48") (pintype "power_in"))
      (node (ref "U3") (pin "64") (pinfunction "VDD_64") (pintype "power_in"))
      (node (ref "U5") (pin "2") (pinfunction "Vout_2") (pintype "passive"))
      (node (ref "U5") (pin "4") (pinfunction "Vout_(tab)_4") (pintype "passive"))
    )
    (net (code "80") (name "unconnected-(U1-NC-Pad5)") (class "Default")
      (node (ref "U1") (pin "5") (pinfunction "NC_5") (pintype "passive"))
    )
    (net (code "81") (name "unconnected-(U1-NC-Pad8)") (class "Default")
      (node (ref "U1") (pin "8") (pinfunction "NC_8") (pintype "passive"))
    )
    (net (code "82") (name "unconnected-(U2-RTS#-Pad4)") (class "Default")
      (node (ref "U2") (pin "4") (pinfunction "RTS#_4") (pintype "passive"))
    )
    (net (code "83") (name "unconnected-(USB1-CC1-Pad4)") (class "Default")
      (node (ref "USB1") (pin "4") (pinfunction "CC1_4") (pintype "passive"))
    )
    (net (code "84") (name "unconnected-(USB1-CC2-Pad10)") (class "Default")
      (node (ref "USB1") (pin "10") (pinfunction "CC2_10") (pintype "passive"))
    )
    (net (code "85") (name "unconnected-(USB1-SBU1-Pad9)") (class "Default")
      (node (ref "USB1") (pin "9") (pinfunction "SBU1_9") (pintype "passive"))
    )
    (net (code "86") (name "unconnected-(USB1-SBU2-Pad3)") (class "Default")
      (node (ref "USB1") (pin "3") (pinfunction "SBU2_3") (pintype "passive"))
    )
    (net (code "87") (name "unconnected-(USB1-VBUS-Pad2)") (class "Default")
      (node (ref "USB1") (pin "2") (pinfunction "VBUS_2") (pintype "passive"))
    )
    (net (code "88") (name "unconnected-(USB1-VBUS-Pad11)") (class "Default")
      (node (ref "USB1") (pin "11") (pinfunction "VBUS_11") (pintype "passive"))
    )
  )
)
